# TPS922053_ch.net
KiCad netlist of a schematic drawn in Altium Designer
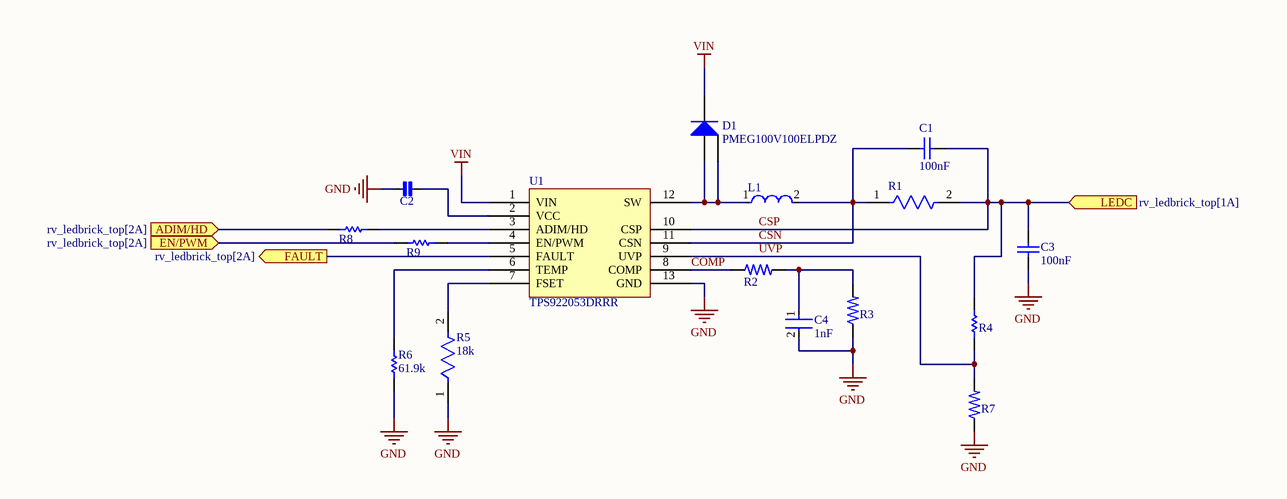
[diagram p0: TPS922053_ch.SchDoc]

(export (version "E")
  (design (tool "Eeschema 10.0.6"))
  (components
    (comp (ref "C1")
      (value "100nF")
      (footprint "CAPC2013X94X50NL20T25")
      (fields (field (name "Comment") "0.1uF X7R 100V 0805"))
      (libsource (lib "StackFoundry LLC") (part "CAP"))
    )
    (comp (ref "C2")
      (value "CAP 1uF 10V X7R 0603")
      (footprint "FP-CL10-IPC_B")
      (description "Cap Ceramic 1uF 10V X7R 10% SMD 0603 125C Paper T/R")
      (libsource (lib "StackFoundry LLC") (part "C-EU"))
    )
    (comp (ref "C3")
      (value "100nF")
      (footprint "CAPC2013X94X50NL20T25")
      (fields (field (name "Comment") "0.1uF X7R 100V 0805"))
      (libsource (lib "StackFoundry LLC") (part "CAP"))
    )
    (comp (ref "C4")
      (value "1nF")
      (footprint "FP-0603-L_1_6_0_15-W_0_81-IPC_B")
      (fields (field (name "Comment") "0.001uF 50V 0603 X7R"))
      (libsource (lib "StackFoundry LLC") (part "02cd4be3c70576c341d710602a673aa"))
    )
    (comp (ref "D1")
      (value "PMEG100V100ELPDZ")
      (footprint "DFN355P580X82-3N")
      (description "Rectifier Diode, Schottky, 1 Phase, 1 Element, 100V V(RRM), Silicon")
      (libsource (lib "StackFoundry LLC") (part "D-AK-2"))
    )
    (comp (ref "L1")
      (value "MWSA0603S-100MT")
      (footprint "FP-IHLP-2525CZ-FP_2_413x3-MFG")
      (description "General Purpose Inductor, 10uH, 20%, 1 Element, Composite-Core, SMD, 2525")
      (fields (field (name "TOLERANCE") "20%"))
      (libsource (lib "StackFoundry LLC") (part "725321dda6339637d4d059423bc1c3c"))
    )
    (comp (ref "R1")
      (value "MFL12HR100FT")
      (footprint "FP-CRA2512-MFG")
      (description "Fixed Resistor, Metal Strip, 3W, 0.1ohm, 5.48V, 1% +/-Tol, 50ppm/Cel, Surface Mount, 2513")
      (libsource (lib "StackFoundry LLC") (part "1029c3af85768c4190bb7ad29bc67b5"))
    )
    (comp (ref "R2")
      (value "1K 0603 1%")
      (footprint "RESC1608-IPC-NL")
      (description "Res Thick Film 0603 1K Ohm 1% 1/10W ±100ppm/°C Molded SMD Punched Carrier T/R")
      (libsource (lib "StackFoundry LLC") (part "R-US"))
    )
    (comp (ref "R3")
      (value "1M 0603 1%")
      (footprint "RESC1608-IPC-NL")
      (description "VISHAY - CRCW06031M00FKEAHP - RES, AEC-Q200, THICK FILM, 1M, 0603")
      (libsource (lib "StackFoundry LLC") (part "R-US"))
    )
    (comp (ref "R4")
      (value "309k 0603 1%")
      (footprint "RESC1608-IPC-NL")
      (description "Res Thick Film 0603 309K Ohm 1% 0.1W(1/10W) ±100ppm/C Molded SMD Paper T/R")
      (libsource (lib "StackFoundry LLC") (part "RES"))
    )
    (comp (ref "R5")
      (value "18k")
      (footprint "FP-CRCW0603-e3-IPC_B")
      (fields
        (field (name "TOLERANCE") "1%")
        (field (name "POWER") "100mW")
        (field (name "Comment") "18k 0603")
      )
      (libsource (lib "StackFoundry LLC") (part "1029c3af85768c4190bb7ad29bc67b5"))
    )
    (comp (ref "R6")
      (value "61.9k")
      (footprint "RESC1608X55X30ML15T15")
      (fields
        (field (name "TOLERANCE") "1%")
        (field (name "POWER") "100mW")
        (field (name "Comment") "ERJ-3EKF6192V")
      )
      (libsource (lib "StackFoundry LLC") (part "RES"))
    )
    (comp (ref "R7")
      (value "100k 0603 1%")
      (footprint "RESC1608-IPC-NL")
      (description "Res Thick Film 1.6 x 0.8 mm 100K Ohm 1% 0.1W(1/10W) 100ppm/ C Molded SMD Paper T/R")
      (libsource (lib "StackFoundry LLC") (part "R-US"))
    )
    (comp (ref "R8")
      (value "10R 0603 1%")
      (footprint "RESC1608-IPC-NL")
      (description "YAGEO (PHYCOMP) - RC0603FR-0710RL - RES, THICK FILM, 10R, 1%, 0.1W, 0603")
      (fields (field (name "TOLERANCE") "1%"))
      (libsource (lib "StackFoundry LLC") (part "RES-2"))
    )
    (comp (ref "R9")
      (value "10R 0603 1%")
      (footprint "RESC1608-IPC-NL")
      (description "YAGEO (PHYCOMP) - RC0603FR-0710RL - RES, THICK FILM, 10R, 1%, 0.1W, 0603")
      (fields (field (name "TOLERANCE") "1%"))
      (libsource (lib "StackFoundry LLC") (part "RES-2"))
    )
    (comp (ref "U1")
      (value "TPS922053DRRR")
      (footprint "SON50P300X100_HS-13N")
      (description "65-V, 2-A buck LED driver with inductive fast dimming and spread spectrum 12-WSON -40 to 125")
      (libsource (lib "StackFoundry LLC") (part "TPS922053DRRR-Symbol-1"))
    )
  )
  (nets
    (net (code "1") (name "/ADIM{slash}HD") (class "Default")
      (node (ref "R8") (pin "1") (pinfunction "1_1") (pintype "passive"))
    )
    (net (code "2") (name "/COMP") (class "Default")
      (node (ref "R2") (pin "1") (pinfunction "1_1") (pintype "passive"))
      (node (ref "U1") (pin "8") (pinfunction "COMP_8") (pintype "passive"))
    )
    (net (code "3") (name "/CSN") (class "Default")
      (node (ref "C1") (pin "2") (pinfunction "2_2") (pintype "passive"))
      (node (ref "L1") (pin "2") (pinfunction "2_2") (pintype "passive"))
      (node (ref "R1") (pin "1") (pinfunction "1_1") (pintype "passive"))
      (node (ref "U1") (pin "11") (pinfunction "CSN_11") (pintype "passive"))
    )
    (net (code "4") (name "/CSP") (class "Default")
      (node (ref "C1") (pin "1") (pinfunction "1_1") (pintype "passive"))
      (node (ref "C3") (pin "2") (pinfunction "2_2") (pintype "passive"))
      (node (ref "R1") (pin "2") (pinfunction "2_2") (pintype "passive"))
      (node (ref "R4") (pin "2") (pinfunction "2_2") (pintype "passive"))
      (node (ref "U1") (pin "10") (pinfunction "CSP_10") (pintype "passive"))
    )
    (net (code "5") (name "/EN{slash}PWM") (class "Default")
      (node (ref "R9") (pin "1") (pinfunction "1_1") (pintype "passive"))
    )
    (net (code "6") (name "/FAULT") (class "Default")
      (node (ref "U1") (pin "5") (pinfunction "FAULT_5") (pintype "passive"))
    )
    (net (code "7") (name "/UVP") (class "Default")
      (node (ref "R4") (pin "1") (pinfunction "1_1") (pintype "passive"))
      (node (ref "R7") (pin "2") (pinfunction "2_2") (pintype "passive"))
      (node (ref "U1") (pin "9") (pinfunction "UVP_9") (pintype "passive"))
    )
    (net (code "8") (name "GND") (class "Default")
      (node (ref "C2") (pin "1") (pinfunction "1_1") (pintype "passive"))
      (node (ref "C3") (pin "1") (pinfunction "1_1") (pintype "passive"))
      (node (ref "C4") (pin "2") (pinfunction "2_2") (pintype "passive"))
      (node (ref "R3") (pin "1") (pinfunction "1_1") (pintype "passive"))
      (node (ref "R5") (pin "1") (pinfunction "1_1") (pintype "passive"))
      (node (ref "R6") (pin "1") (pinfunction "1_1") (pintype "passive"))
      (node (ref "R7") (pin "1") (pinfunction "1_1") (pintype "passive"))
      (node (ref "U1") (pin "13") (pinfunction "GND_13") (pintype "power_in"))
    )
    (net (code "9") (name "Net-(C4-Pad1)") (class "Default")
      (node (ref "C4") (pin "1") (pinfunction "1_1") (pintype "passive"))
      (node (ref "R2") (pin "2") (pinfunction "2_2") (pintype "passive"))
      (node (ref "R3") (pin "2") (pinfunction "2_2") (pintype "passive"))
    )
    (net (code "10") (name "Net-(D1-A)") (class "Default")
      (node (ref "D1") (pin "1") (pinfunction "A_1") (pintype "passive"))
      (node (ref "D1") (pin "2") (pinfunction "A2_2") (pintype "passive"))
      (node (ref "L1") (pin "1") (pinfunction "1_1") (pintype "passive"))
      (node (ref "U1") (pin "12") (pinfunction "SW_12") (pintype "passive"))
    )
    (net (code "11") (name "Net-(U1-ADIM{slash}HD)") (class "Default")
      (node (ref "R8") (pin "2") (pinfunction "2_2") (pintype "passive"))
      (node (ref "U1") (pin "3") (pinfunction "ADIM/HD_3") (pintype "passive"))
    )
    (net (code "12") (name "Net-(U1-EN{slash}PWM)") (class "Default")
      (node (ref "R9") (pin "2") (pinfunction "2_2") (pintype "passive"))
      (node (ref "U1") (pin "4") (pinfunction "EN/PWM_4") (pintype "passive"))
    )
    (net (code "13") (name "Net-(U1-FSET)") (class "Default")
      (node (ref "R5") (pin "2") (pinfunction "2_2") (pintype "passive"))
      (node (ref "U1") (pin "7") (pinfunction "FSET_7") (pintype "passive"))
    )
    (net (code "14") (name "Net-(U1-TEMP)") (class "Default")
      (node (ref "R6") (pin "2") (pinfunction "2_2") (pintype "passive"))
      (node (ref "U1") (pin "6") (pinfunction "TEMP_6") (pintype "passive"))
    )
    (net (code "15") (name "Net-(U1-VCC)") (class "Default")
      (node (ref "C2") (pin "2") (pinfunction "2_2") (pintype "passive"))
      (node (ref "U1") (pin "2") (pinfunction "VCC_2") (pintype "passive"))
    )
    (net (code "16") (name "VIN") (class "Default")
      (node (ref "D1") (pin "3") (pinfunction "K_3") (pintype "passive"))
      (node (ref "U1") (pin "1") (pinfunction "VIN_1") (pintype "power_in"))
    )
  )
)
